# IC_Adapter_2x20_multi.net
KiCad netlist of a schematic drawn in EAGLE
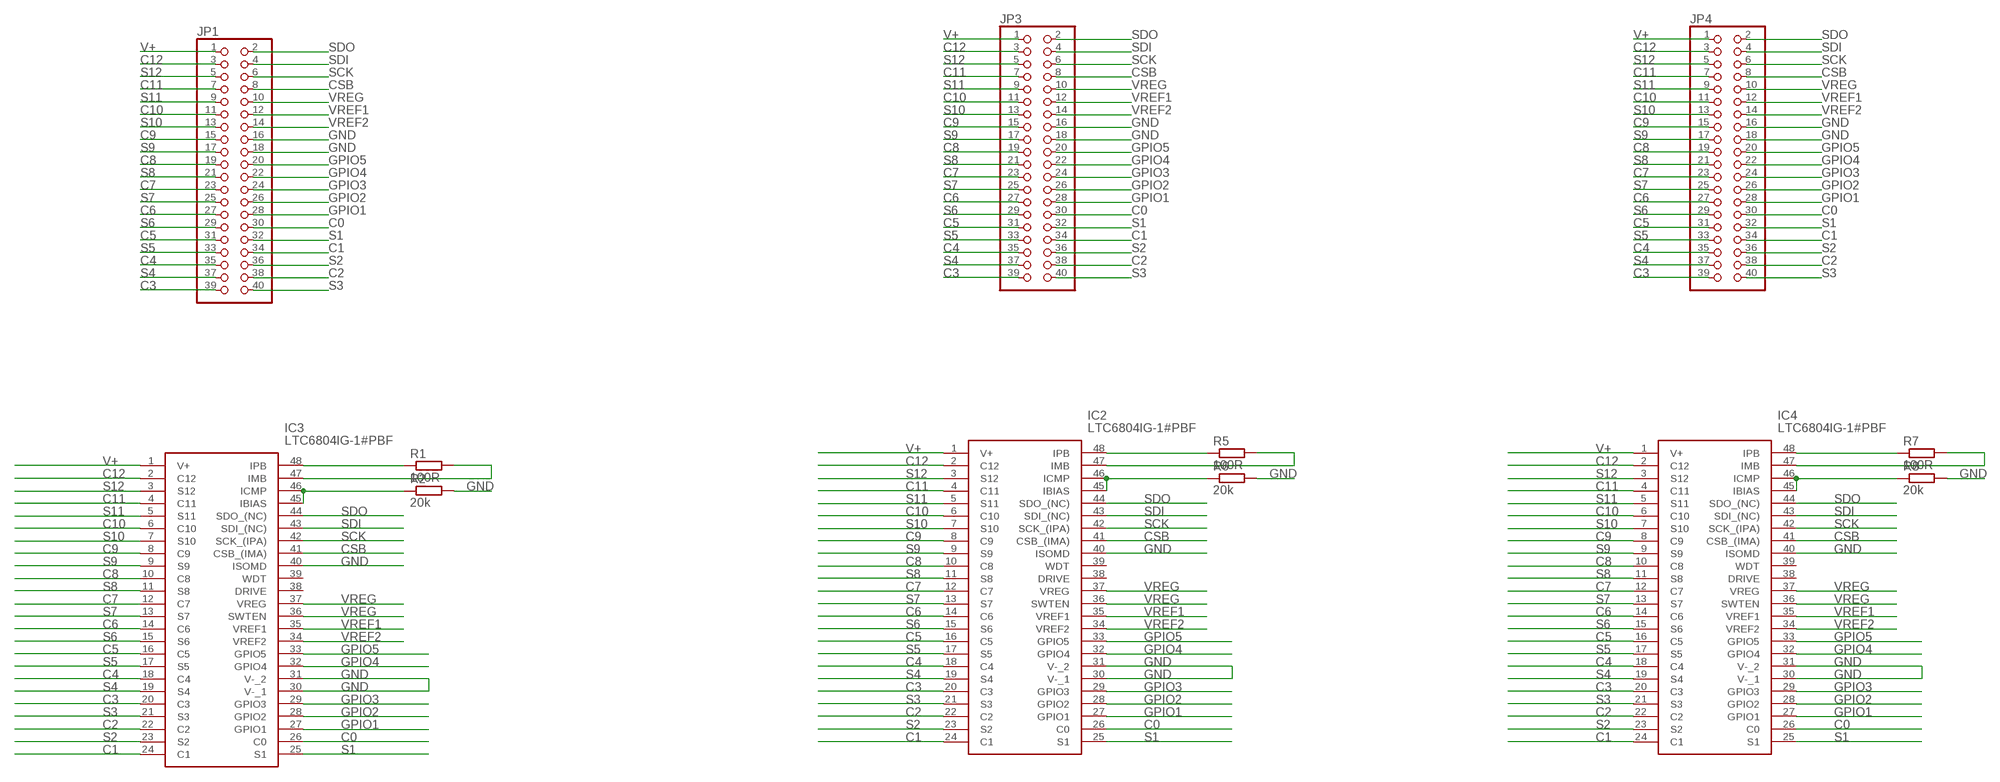
[diagram p0: schematic, sheet 1]

(export (version "E")
  (design (tool "Eeschema 10.0.6"))
  (components
    (comp (ref "IC2")
      (value "LTC6804IG-1#PBF")
      (footprint "eagle-import:SOP50P780X200-48N")
      (fields (field (name "MOUSER_PART_NUMBER") "584-LTC6804IG-1#PBF"))
      (libsource (lib "eagle-import") (part "LTC6804IG-1#PBF"))
    )
    (comp (ref "IC3")
      (value "LTC6804IG-1#PBF")
      (footprint "eagle-import:SOP50P780X200-48N")
      (fields (field (name "MOUSER_PART_NUMBER") "584-LTC6804IG-1#PBF"))
      (libsource (lib "eagle-import") (part "LTC6804IG-1#PBF"))
    )
    (comp (ref "IC4")
      (value "LTC6804IG-1#PBF")
      (footprint "eagle-import:SOP50P780X200-48N")
      (fields (field (name "MOUSER_PART_NUMBER") "584-LTC6804IG-1#PBF"))
      (libsource (lib "eagle-import") (part "LTC6804IG-1#PBF"))
    )
    (comp (ref "JP1")
      (value "PINHD-2X20")
      (footprint "eagle-import:2X20")
      (libsource (lib "eagle-import") (part "PINHD-2X20"))
    )
    (comp (ref "JP3")
      (value "PINHD-2X20")
      (footprint "eagle-import:2X20")
      (libsource (lib "eagle-import") (part "PINHD-2X20"))
    )
    (comp (ref "JP4")
      (value "PINHD-2X20")
      (footprint "eagle-import:2X20")
      (libsource (lib "eagle-import") (part "PINHD-2X20"))
    )
    (comp (ref "R1")
      (value "100R")
      (footprint "eagle-import:R0805")
      (libsource (lib "eagle-import") (part "R-EU_R0805"))
    )
    (comp (ref "R2")
      (value "20k")
      (footprint "eagle-import:R0805")
      (libsource (lib "eagle-import") (part "R-EU_R0805"))
    )
    (comp (ref "R5")
      (value "100R")
      (footprint "eagle-import:R0805")
      (libsource (lib "eagle-import") (part "R-EU_R0805"))
    )
    (comp (ref "R6")
      (value "20k")
      (footprint "eagle-import:R0805")
      (libsource (lib "eagle-import") (part "R-EU_R0805"))
    )
    (comp (ref "R7")
      (value "100R")
      (footprint "eagle-import:R0805")
      (libsource (lib "eagle-import") (part "R-EU_R0805"))
    )
    (comp (ref "R8")
      (value "20k")
      (footprint "eagle-import:R0805")
      (libsource (lib "eagle-import") (part "R-EU_R0805"))
    )
  )
  (nets
    (net (code "1") (name "/C0") (class "Default")
      (node (ref "IC2") (pin "26") (pinfunction "C0_26") (pintype "bidirectional"))
      (node (ref "IC3") (pin "26") (pinfunction "C0_26") (pintype "bidirectional"))
      (node (ref "IC4") (pin "26") (pinfunction "C0_26") (pintype "bidirectional"))
      (node (ref "JP1") (pin "30") (pinfunction "30_30") (pintype "passive"))
      (node (ref "JP3") (pin "30") (pinfunction "30_30") (pintype "passive"))
      (node (ref "JP4") (pin "30") (pinfunction "30_30") (pintype "passive"))
    )
    (net (code "2") (name "/C1") (class "Default")
      (node (ref "IC2") (pin "24") (pinfunction "C1_24") (pintype "bidirectional"))
      (node (ref "IC3") (pin "24") (pinfunction "C1_24") (pintype "bidirectional"))
      (node (ref "IC4") (pin "24") (pinfunction "C1_24") (pintype "bidirectional"))
      (node (ref "JP1") (pin "34") (pinfunction "34_34") (pintype "passive"))
      (node (ref "JP3") (pin "34") (pinfunction "34_34") (pintype "passive"))
      (node (ref "JP4") (pin "34") (pinfunction "34_34") (pintype "passive"))
    )
    (net (code "3") (name "/C2") (class "Default")
      (node (ref "IC2") (pin "22") (pinfunction "C2_22") (pintype "bidirectional"))
      (node (ref "IC3") (pin "22") (pinfunction "C2_22") (pintype "bidirectional"))
      (node (ref "IC4") (pin "22") (pinfunction "C2_22") (pintype "bidirectional"))
      (node (ref "JP1") (pin "38") (pinfunction "38_38") (pintype "passive"))
      (node (ref "JP3") (pin "38") (pinfunction "38_38") (pintype "passive"))
      (node (ref "JP4") (pin "38") (pinfunction "38_38") (pintype "passive"))
    )
    (net (code "4") (name "/C3") (class "Default")
      (node (ref "IC2") (pin "20") (pinfunction "C3_20") (pintype "bidirectional"))
      (node (ref "IC3") (pin "20") (pinfunction "C3_20") (pintype "bidirectional"))
      (node (ref "IC4") (pin "20") (pinfunction "C3_20") (pintype "bidirectional"))
      (node (ref "JP1") (pin "39") (pinfunction "39_39") (pintype "passive"))
      (node (ref "JP3") (pin "39") (pinfunction "39_39") (pintype "passive"))
      (node (ref "JP4") (pin "39") (pinfunction "39_39") (pintype "passive"))
    )
    (net (code "5") (name "/C4") (class "Default")
      (node (ref "IC2") (pin "18") (pinfunction "C4_18") (pintype "bidirectional"))
      (node (ref "IC3") (pin "18") (pinfunction "C4_18") (pintype "bidirectional"))
      (node (ref "IC4") (pin "18") (pinfunction "C4_18") (pintype "bidirectional"))
      (node (ref "JP1") (pin "35") (pinfunction "35_35") (pintype "passive"))
      (node (ref "JP3") (pin "35") (pinfunction "35_35") (pintype "passive"))
      (node (ref "JP4") (pin "35") (pinfunction "35_35") (pintype "passive"))
    )
    (net (code "6") (name "/C5") (class "Default")
      (node (ref "IC2") (pin "16") (pinfunction "C5_16") (pintype "bidirectional"))
      (node (ref "IC3") (pin "16") (pinfunction "C5_16") (pintype "bidirectional"))
      (node (ref "IC4") (pin "16") (pinfunction "C5_16") (pintype "bidirectional"))
      (node (ref "JP1") (pin "31") (pinfunction "31_31") (pintype "passive"))
      (node (ref "JP3") (pin "31") (pinfunction "31_31") (pintype "passive"))
      (node (ref "JP4") (pin "31") (pinfunction "31_31") (pintype "passive"))
    )
    (net (code "7") (name "/C6") (class "Default")
      (node (ref "IC2") (pin "14") (pinfunction "C6_14") (pintype "bidirectional"))
      (node (ref "IC3") (pin "14") (pinfunction "C6_14") (pintype "bidirectional"))
      (node (ref "IC4") (pin "14") (pinfunction "C6_14") (pintype "bidirectional"))
      (node (ref "JP1") (pin "27") (pinfunction "27_27") (pintype "passive"))
      (node (ref "JP3") (pin "27") (pinfunction "27_27") (pintype "passive"))
      (node (ref "JP4") (pin "27") (pinfunction "27_27") (pintype "passive"))
    )
    (net (code "8") (name "/C7") (class "Default")
      (node (ref "IC2") (pin "12") (pinfunction "C7_12") (pintype "bidirectional"))
      (node (ref "IC3") (pin "12") (pinfunction "C7_12") (pintype "bidirectional"))
      (node (ref "IC4") (pin "12") (pinfunction "C7_12") (pintype "bidirectional"))
      (node (ref "JP1") (pin "23") (pinfunction "23_23") (pintype "passive"))
      (node (ref "JP3") (pin "23") (pinfunction "23_23") (pintype "passive"))
      (node (ref "JP4") (pin "23") (pinfunction "23_23") (pintype "passive"))
    )
    (net (code "9") (name "/C8") (class "Default")
      (node (ref "IC2") (pin "10") (pinfunction "C8_10") (pintype "bidirectional"))
      (node (ref "IC3") (pin "10") (pinfunction "C8_10") (pintype "bidirectional"))
      (node (ref "IC4") (pin "10") (pinfunction "C8_10") (pintype "bidirectional"))
      (node (ref "JP1") (pin "19") (pinfunction "19_19") (pintype "passive"))
      (node (ref "JP3") (pin "19") (pinfunction "19_19") (pintype "passive"))
      (node (ref "JP4") (pin "19") (pinfunction "19_19") (pintype "passive"))
    )
    (net (code "10") (name "/C9") (class "Default")
      (node (ref "IC2") (pin "8") (pinfunction "C9_8") (pintype "bidirectional"))
      (node (ref "IC3") (pin "8") (pinfunction "C9_8") (pintype "bidirectional"))
      (node (ref "IC4") (pin "8") (pinfunction "C9_8") (pintype "bidirectional"))
      (node (ref "JP1") (pin "15") (pinfunction "15_15") (pintype "passive"))
      (node (ref "JP3") (pin "15") (pinfunction "15_15") (pintype "passive"))
      (node (ref "JP4") (pin "15") (pinfunction "15_15") (pintype "passive"))
    )
    (net (code "11") (name "/C10") (class "Default")
      (node (ref "IC2") (pin "6") (pinfunction "C10_6") (pintype "bidirectional"))
      (node (ref "IC3") (pin "6") (pinfunction "C10_6") (pintype "bidirectional"))
      (node (ref "IC4") (pin "6") (pinfunction "C10_6") (pintype "bidirectional"))
      (node (ref "JP1") (pin "11") (pinfunction "11_11") (pintype "passive"))
      (node (ref "JP3") (pin "11") (pinfunction "11_11") (pintype "passive"))
      (node (ref "JP4") (pin "11") (pinfunction "11_11") (pintype "passive"))
    )
    (net (code "12") (name "/C11") (class "Default")
      (node (ref "IC2") (pin "4") (pinfunction "C11_4") (pintype "bidirectional"))
      (node (ref "IC3") (pin "4") (pinfunction "C11_4") (pintype "bidirectional"))
      (node (ref "IC4") (pin "4") (pinfunction "C11_4") (pintype "bidirectional"))
      (node (ref "JP1") (pin "7") (pinfunction "7_7") (pintype "passive"))
      (node (ref "JP3") (pin "7") (pinfunction "7_7") (pintype "passive"))
      (node (ref "JP4") (pin "7") (pinfunction "7_7") (pintype "passive"))
    )
    (net (code "13") (name "/C12") (class "Default")
      (node (ref "IC2") (pin "2") (pinfunction "C12_2") (pintype "bidirectional"))
      (node (ref "IC3") (pin "2") (pinfunction "C12_2") (pintype "bidirectional"))
      (node (ref "IC4") (pin "2") (pinfunction "C12_2") (pintype "bidirectional"))
      (node (ref "JP1") (pin "3") (pinfunction "3_3") (pintype "passive"))
      (node (ref "JP3") (pin "3") (pinfunction "3_3") (pintype "passive"))
      (node (ref "JP4") (pin "3") (pinfunction "3_3") (pintype "passive"))
    )
    (net (code "14") (name "/CSB") (class "Default")
      (node (ref "IC2") (pin "41") (pinfunction "CSB_(IMA)_41") (pintype "bidirectional"))
      (node (ref "IC3") (pin "41") (pinfunction "CSB_(IMA)_41") (pintype "bidirectional"))
      (node (ref "IC4") (pin "41") (pinfunction "CSB_(IMA)_41") (pintype "bidirectional"))
      (node (ref "JP1") (pin "8") (pinfunction "8_8") (pintype "passive"))
      (node (ref "JP3") (pin "8") (pinfunction "8_8") (pintype "passive"))
      (node (ref "JP4") (pin "8") (pinfunction "8_8") (pintype "passive"))
    )
    (net (code "15") (name "/GND") (class "Default")
      (node (ref "IC2") (pin "30") (pinfunction "V-_1_30") (pintype "bidirectional"))
      (node (ref "IC2") (pin "31") (pinfunction "V-_2_31") (pintype "bidirectional"))
      (node (ref "IC2") (pin "40") (pinfunction "ISOMD_40") (pintype "bidirectional"))
      (node (ref "IC3") (pin "30") (pinfunction "V-_1_30") (pintype "bidirectional"))
      (node (ref "IC3") (pin "31") (pinfunction "V-_2_31") (pintype "bidirectional"))
      (node (ref "IC3") (pin "40") (pinfunction "ISOMD_40") (pintype "bidirectional"))
      (node (ref "IC4") (pin "30") (pinfunction "V-_1_30") (pintype "bidirectional"))
      (node (ref "IC4") (pin "31") (pinfunction "V-_2_31") (pintype "bidirectional"))
      (node (ref "IC4") (pin "40") (pinfunction "ISOMD_40") (pintype "bidirectional"))
      (node (ref "JP1") (pin "16") (pinfunction "16_16") (pintype "passive"))
      (node (ref "JP1") (pin "18") (pinfunction "18_18") (pintype "passive"))
      (node (ref "JP3") (pin "16") (pinfunction "16_16") (pintype "passive"))
      (node (ref "JP3") (pin "18") (pinfunction "18_18") (pintype "passive"))
      (node (ref "JP4") (pin "16") (pinfunction "16_16") (pintype "passive"))
      (node (ref "JP4") (pin "18") (pinfunction "18_18") (pintype "passive"))
      (node (ref "R2") (pin "2") (pinfunction "2_2") (pintype "passive"))
      (node (ref "R6") (pin "2") (pinfunction "2_2") (pintype "passive"))
      (node (ref "R8") (pin "2") (pinfunction "2_2") (pintype "passive"))
    )
    (net (code "16") (name "/GPIO1") (class "Default")
      (node (ref "IC2") (pin "27") (pinfunction "GPIO1_27") (pintype "bidirectional"))
      (node (ref "IC3") (pin "27") (pinfunction "GPIO1_27") (pintype "bidirectional"))
      (node (ref "IC4") (pin "27") (pinfunction "GPIO1_27") (pintype "bidirectional"))
      (node (ref "JP1") (pin "28") (pinfunction "28_28") (pintype "passive"))
      (node (ref "JP3") (pin "28") (pinfunction "28_28") (pintype "passive"))
      (node (ref "JP4") (pin "28") (pinfunction "28_28") (pintype "passive"))
    )
    (net (code "17") (name "/GPIO2") (class "Default")
      (node (ref "IC2") (pin "28") (pinfunction "GPIO2_28") (pintype "bidirectional"))
      (node (ref "IC3") (pin "28") (pinfunction "GPIO2_28") (pintype "bidirectional"))
      (node (ref "IC4") (pin "28") (pinfunction "GPIO2_28") (pintype "bidirectional"))
      (node (ref "JP1") (pin "26") (pinfunction "26_26") (pintype "passive"))
      (node (ref "JP3") (pin "26") (pinfunction "26_26") (pintype "passive"))
      (node (ref "JP4") (pin "26") (pinfunction "26_26") (pintype "passive"))
    )
    (net (code "18") (name "/GPIO3") (class "Default")
      (node (ref "IC2") (pin "29") (pinfunction "GPIO3_29") (pintype "bidirectional"))
      (node (ref "IC3") (pin "29") (pinfunction "GPIO3_29") (pintype "bidirectional"))
      (node (ref "IC4") (pin "29") (pinfunction "GPIO3_29") (pintype "bidirectional"))
      (node (ref "JP1") (pin "24") (pinfunction "24_24") (pintype "passive"))
      (node (ref "JP3") (pin "24") (pinfunction "24_24") (pintype "passive"))
      (node (ref "JP4") (pin "24") (pinfunction "24_24") (pintype "passive"))
    )
    (net (code "19") (name "/GPIO4") (class "Default")
      (node (ref "IC2") (pin "32") (pinfunction "GPIO4_32") (pintype "bidirectional"))
      (node (ref "IC3") (pin "32") (pinfunction "GPIO4_32") (pintype "bidirectional"))
      (node (ref "IC4") (pin "32") (pinfunction "GPIO4_32") (pintype "bidirectional"))
      (node (ref "JP1") (pin "22") (pinfunction "22_22") (pintype "passive"))
      (node (ref "JP3") (pin "22") (pinfunction "22_22") (pintype "passive"))
      (node (ref "JP4") (pin "22") (pinfunction "22_22") (pintype "passive"))
    )
    (net (code "20") (name "/GPIO5") (class "Default")
      (node (ref "IC2") (pin "33") (pinfunction "GPIO5_33") (pintype "bidirectional"))
      (node (ref "IC3") (pin "33") (pinfunction "GPIO5_33") (pintype "bidirectional"))
      (node (ref "IC4") (pin "33") (pinfunction "GPIO5_33") (pintype "bidirectional"))
      (node (ref "JP1") (pin "20") (pinfunction "20_20") (pintype "passive"))
      (node (ref "JP3") (pin "20") (pinfunction "20_20") (pintype "passive"))
      (node (ref "JP4") (pin "20") (pinfunction "20_20") (pintype "passive"))
    )
    (net (code "21") (name "/S1") (class "Default")
      (node (ref "IC2") (pin "25") (pinfunction "S1_25") (pintype "bidirectional"))
      (node (ref "IC3") (pin "25") (pinfunction "S1_25") (pintype "bidirectional"))
      (node (ref "IC4") (pin "25") (pinfunction "S1_25") (pintype "bidirectional"))
      (node (ref "JP1") (pin "32") (pinfunction "32_32") (pintype "passive"))
      (node (ref "JP3") (pin "32") (pinfunction "32_32") (pintype "passive"))
      (node (ref "JP4") (pin "32") (pinfunction "32_32") (pintype "passive"))
    )
    (net (code "22") (name "/S2") (class "Default")
      (node (ref "IC2") (pin "23") (pinfunction "S2_23") (pintype "bidirectional"))
      (node (ref "IC3") (pin "23") (pinfunction "S2_23") (pintype "bidirectional"))
      (node (ref "IC4") (pin "23") (pinfunction "S2_23") (pintype "bidirectional"))
      (node (ref "JP1") (pin "36") (pinfunction "36_36") (pintype "passive"))
      (node (ref "JP3") (pin "36") (pinfunction "36_36") (pintype "passive"))
      (node (ref "JP4") (pin "36") (pinfunction "36_36") (pintype "passive"))
    )
    (net (code "23") (name "/S3") (class "Default")
      (node (ref "IC2") (pin "21") (pinfunction "S3_21") (pintype "bidirectional"))
      (node (ref "IC3") (pin "21") (pinfunction "S3_21") (pintype "bidirectional"))
      (node (ref "IC4") (pin "21") (pinfunction "S3_21") (pintype "bidirectional"))
      (node (ref "JP1") (pin "40") (pinfunction "40_40") (pintype "passive"))
      (node (ref "JP3") (pin "40") (pinfunction "40_40") (pintype "passive"))
      (node (ref "JP4") (pin "40") (pinfunction "40_40") (pintype "passive"))
    )
    (net (code "24") (name "/S4") (class "Default")
      (node (ref "IC2") (pin "19") (pinfunction "S4_19") (pintype "bidirectional"))
      (node (ref "IC3") (pin "19") (pinfunction "S4_19") (pintype "bidirectional"))
      (node (ref "IC4") (pin "19") (pinfunction "S4_19") (pintype "bidirectional"))
      (node (ref "JP1") (pin "37") (pinfunction "37_37") (pintype "passive"))
      (node (ref "JP3") (pin "37") (pinfunction "37_37") (pintype "passive"))
      (node (ref "JP4") (pin "37") (pinfunction "37_37") (pintype "passive"))
    )
    (net (code "25") (name "/S5") (class "Default")
      (node (ref "IC2") (pin "17") (pinfunction "S5_17") (pintype "bidirectional"))
      (node (ref "IC3") (pin "17") (pinfunction "S5_17") (pintype "bidirectional"))
      (node (ref "IC4") (pin "17") (pinfunction "S5_17") (pintype "bidirectional"))
      (node (ref "JP1") (pin "33") (pinfunction "33_33") (pintype "passive"))
      (node (ref "JP3") (pin "33") (pinfunction "33_33") (pintype "passive"))
      (node (ref "JP4") (pin "33") (pinfunction "33_33") (pintype "passive"))
    )
    (net (code "26") (name "/S6") (class "Default")
      (node (ref "IC2") (pin "15") (pinfunction "S6_15") (pintype "bidirectional"))
      (node (ref "IC3") (pin "15") (pinfunction "S6_15") (pintype "bidirectional"))
      (node (ref "IC4") (pin "15") (pinfunction "S6_15") (pintype "bidirectional"))
      (node (ref "JP1") (pin "29") (pinfunction "29_29") (pintype "passive"))
      (node (ref "JP3") (pin "29") (pinfunction "29_29") (pintype "passive"))
      (node (ref "JP4") (pin "29") (pinfunction "29_29") (pintype "passive"))
    )
    (net (code "27") (name "/S7") (class "Default")
      (node (ref "IC2") (pin "13") (pinfunction "S7_13") (pintype "bidirectional"))
      (node (ref "IC3") (pin "13") (pinfunction "S7_13") (pintype "bidirectional"))
      (node (ref "IC4") (pin "13") (pinfunction "S7_13") (pintype "bidirectional"))
      (node (ref "JP1") (pin "25") (pinfunction "25_25") (pintype "passive"))
      (node (ref "JP3") (pin "25") (pinfunction "25_25") (pintype "passive"))
      (node (ref "JP4") (pin "25") (pinfunction "25_25") (pintype "passive"))
    )
    (net (code "28") (name "/S8") (class "Default")
      (node (ref "IC2") (pin "11") (pinfunction "S8_11") (pintype "bidirectional"))
      (node (ref "IC3") (pin "11") (pinfunction "S8_11") (pintype "bidirectional"))
      (node (ref "IC4") (pin "11") (pinfunction "S8_11") (pintype "bidirectional"))
      (node (ref "JP1") (pin "21") (pinfunction "21_21") (pintype "passive"))
      (node (ref "JP3") (pin "21") (pinfunction "21_21") (pintype "passive"))
      (node (ref "JP4") (pin "21") (pinfunction "21_21") (pintype "passive"))
    )
    (net (code "29") (name "/S9") (class "Default")
      (node (ref "IC2") (pin "9") (pinfunction "S9_9") (pintype "bidirectional"))
      (node (ref "IC3") (pin "9") (pinfunction "S9_9") (pintype "bidirectional"))
      (node (ref "IC4") (pin "9") (pinfunction "S9_9") (pintype "bidirectional"))
      (node (ref "JP1") (pin "17") (pinfunction "17_17") (pintype "passive"))
      (node (ref "JP3") (pin "17") (pinfunction "17_17") (pintype "passive"))
      (node (ref "JP4") (pin "17") (pinfunction "17_17") (pintype "passive"))
    )
    (net (code "30") (name "/S10") (class "Default")
      (node (ref "IC2") (pin "7") (pinfunction "S10_7") (pintype "bidirectional"))
      (node (ref "IC3") (pin "7") (pinfunction "S10_7") (pintype "bidirectional"))
      (node (ref "IC4") (pin "7") (pinfunction "S10_7") (pintype "bidirectional"))
      (node (ref "JP1") (pin "13") (pinfunction "13_13") (pintype "passive"))
      (node (ref "JP3") (pin "13") (pinfunction "13_13") (pintype "passive"))
      (node (ref "JP4") (pin "13") (pinfunction "13_13") (pintype "passive"))
    )
    (net (code "31") (name "/S11") (class "Default")
      (node (ref "IC2") (pin "5") (pinfunction "S11_5") (pintype "bidirectional"))
      (node (ref "IC3") (pin "5") (pinfunction "S11_5") (pintype "bidirectional"))
      (node (ref "IC4") (pin "5") (pinfunction "S11_5") (pintype "bidirectional"))
      (node (ref "JP1") (pin "9") (pinfunction "9_9") (pintype "passive"))
      (node (ref "JP3") (pin "9") (pinfunction "9_9") (pintype "passive"))
      (node (ref "JP4") (pin "9") (pinfunction "9_9") (pintype "passive"))
    )
    (net (code "32") (name "/S12") (class "Default")
      (node (ref "IC2") (pin "3") (pinfunction "S12_3") (pintype "bidirectional"))
      (node (ref "IC3") (pin "3") (pinfunction "S12_3") (pintype "bidirectional"))
      (node (ref "IC4") (pin "3") (pinfunction "S12_3") (pintype "bidirectional"))
      (node (ref "JP1") (pin "5") (pinfunction "5_5") (pintype "passive"))
      (node (ref "JP3") (pin "5") (pinfunction "5_5") (pintype "passive"))
      (node (ref "JP4") (pin "5") (pinfunction "5_5") (pintype "passive"))
    )
    (net (code "33") (name "/SCK") (class "Default")
      (node (ref "IC2") (pin "42") (pinfunction "SCK_(IPA)_42") (pintype "bidirectional"))
      (node (ref "IC3") (pin "42") (pinfunction "SCK_(IPA)_42") (pintype "bidirectional"))
      (node (ref "IC4") (pin "42") (pinfunction "SCK_(IPA)_42") (pintype "bidirectional"))
      (node (ref "JP1") (pin "6") (pinfunction "6_6") (pintype "passive"))
      (node (ref "JP3") (pin "6") (pinfunction "6_6") (pintype "passive"))
      (node (ref "JP4") (pin "6") (pinfunction "6_6") (pintype "passive"))
    )
    (net (code "34") (name "/SDI") (class "Default")
      (node (ref "IC2") (pin "43") (pinfunction "SDI_(NC)_43") (pintype "bidirectional"))
      (node (ref "IC3") (pin "43") (pinfunction "SDI_(NC)_43") (pintype "bidirectional"))
      (node (ref "IC4") (pin "43") (pinfunction "SDI_(NC)_43") (pintype "bidirectional"))
      (node (ref "JP1") (pin "4") (pinfunction "4_4") (pintype "passive"))
      (node (ref "JP3") (pin "4") (pinfunction "4_4") (pintype "passive"))
      (node (ref "JP4") (pin "4") (pinfunction "4_4") (pintype "passive"))
    )
    (net (code "35") (name "/SDO") (class "Default")
      (node (ref "IC2") (pin "44") (pinfunction "SDO_(NC)_44") (pintype "bidirectional"))
      (node (ref "IC3") (pin "44") (pinfunction "SDO_(NC)_44") (pintype "bidirectional"))
      (node (ref "IC4") (pin "44") (pinfunction "SDO_(NC)_44") (pintype "bidirectional"))
      (node (ref "JP1") (pin "2") (pinfunction "2_2") (pintype "passive"))
      (node (ref "JP3") (pin "2") (pinfunction "2_2") (pintype "passive"))
      (node (ref "JP4") (pin "2") (pinfunction "2_2") (pintype "passive"))
    )
    (net (code "36") (name "/V+") (class "Default")
      (node (ref "IC2") (pin "1") (pinfunction "V+_1") (pintype "bidirectional"))
      (node (ref "IC3") (pin "1") (pinfunction "V+_1") (pintype "bidirectional"))
      (node (ref "IC4") (pin "1") (pinfunction "V+_1") (pintype "bidirectional"))
      (node (ref "JP1") (pin "1") (pinfunction "1_1") (pintype "passive"))
      (node (ref "JP3") (pin "1") (pinfunction "1_1") (pintype "passive"))
      (node (ref "JP4") (pin "1") (pinfunction "1_1") (pintype "passive"))
    )
    (net (code "37") (name "/VREF1") (class "Default")
      (node (ref "IC2") (pin "35") (pinfunction "VREF1_35") (pintype "bidirectional"))
      (node (ref "IC3") (pin "35") (pinfunction "VREF1_35") (pintype "bidirectional"))
      (node (ref "IC4") (pin "35") (pinfunction "VREF1_35") (pintype "bidirectional"))
      (node (ref "JP1") (pin "12") (pinfunction "12_12") (pintype "passive"))
      (node (ref "JP3") (pin "12") (pinfunction "12_12") (pintype "passive"))
      (node (ref "JP4") (pin "12") (pinfunction "12_12") (pintype "passive"))
    )
    (net (code "38") (name "/VREF2") (class "Default")
      (node (ref "IC2") (pin "34") (pinfunction "VREF2_34") (pintype "bidirectional"))
      (node (ref "IC3") (pin "34") (pinfunction "VREF2_34") (pintype "bidirectional"))
      (node (ref "IC4") (pin "34") (pinfunction "VREF2_34") (pintype "bidirectional"))
      (node (ref "JP1") (pin "14") (pinfunction "14_14") (pintype "passive"))
      (node (ref "JP3") (pin "14") (pinfunction "14_14") (pintype "passive"))
      (node (ref "JP4") (pin "14") (pinfunction "14_14") (pintype "passive"))
    )
    (net (code "39") (name "/VREG") (class "Default")
      (node (ref "IC2") (pin "36") (pinfunction "SWTEN_36") (pintype "bidirectional"))
      (node (ref "IC2") (pin "37") (pinfunction "VREG_37") (pintype "bidirectional"))
      (node (ref "IC3") (pin "36") (pinfunction "SWTEN_36") (pintype "bidirectional"))
      (node (ref "IC3") (pin "37") (pinfunction "VREG_37") (pintype "bidirectional"))
      (node (ref "IC4") (pin "36") (pinfunction "SWTEN_36") (pintype "bidirectional"))
      (node (ref "IC4") (pin "37") (pinfunction "VREG_37") (pintype "bidirectional"))
      (node (ref "JP1") (pin "10") (pinfunction "10_10") (pintype "passive"))
      (node (ref "JP3") (pin "10") (pinfunction "10_10") (pintype "passive"))
      (node (ref "JP4") (pin "10") (pinfunction "10_10") (pintype "passive"))
    )
    (net (code "40") (name "Net-(IC2-IBIAS)") (class "Default")
      (node (ref "IC2") (pin "45") (pinfunction "IBIAS_45") (pintype "bidirectional"))
      (node (ref "IC2") (pin "46") (pinfunction "ICMP_46") (pintype "bidirectional"))
      (node (ref "R6") (pin "1") (pinfunction "1_1") (pintype "passive"))
    )
    (net (code "41") (name "Net-(IC2-IMB)") (class "Default")
      (node (ref "IC2") (pin "47") (pinfunction "IMB_47") (pintype "bidirectional"))
      (node (ref "R5") (pin "2") (pinfunction "2_2") (pintype "passive"))
    )
    (net (code "42") (name "Net-(IC2-IPB)") (class "Default")
      (node (ref "IC2") (pin "48") (pinfunction "IPB_48") (pintype "bidirectional"))
      (node (ref "R5") (pin "1") (pinfunction "1_1") (pintype "passive"))
    )
    (net (code "43") (name "Net-(IC3-IBIAS)") (class "Default")
      (node (ref "IC3") (pin "45") (pinfunction "IBIAS_45") (pintype "bidirectional"))
      (node (ref "IC3") (pin "46") (pinfunction "ICMP_46") (pintype "bidirectional"))
      (node (ref "R2") (pin "1") (pinfunction "1_1") (pintype "passive"))
    )
    (net (code "44") (name "Net-(IC3-IMB)") (class "Default")
      (node (ref "IC3") (pin "47") (pinfunction "IMB_47") (pintype "bidirectional"))
      (node (ref "R1") (pin "2") (pinfunction "2_2") (pintype "passive"))
    )
    (net (code "45") (name "Net-(IC3-IPB)") (class "Default")
      (node (ref "IC3") (pin "48") (pinfunction "IPB_48") (pintype "bidirectional"))
      (node (ref "R1") (pin "1") (pinfunction "1_1") (pintype "passive"))
    )
    (net (code "46") (name "Net-(IC4-IBIAS)") (class "Default")
      (node (ref "IC4") (pin "45") (pinfunction "IBIAS_45") (pintype "bidirectional"))
      (node (ref "IC4") (pin "46") (pinfunction "ICMP_46") (pintype "bidirectional"))
      (node (ref "R8") (pin "1") (pinfunction "1_1") (pintype "passive"))
    )
    (net (code "47") (name "Net-(IC4-IMB)") (class "Default")
      (node (ref "IC4") (pin "47") (pinfunction "IMB_47") (pintype "bidirectional"))
      (node (ref "R7") (pin "2") (pinfunction "2_2") (pintype "passive"))
    )
    (net (code "48") (name "Net-(IC4-IPB)") (class "Default")
      (node (ref "IC4") (pin "48") (pinfunction "IPB_48") (pintype "bidirectional"))
      (node (ref "R7") (pin "1") (pinfunction "1_1") (pintype "passive"))
    )
    (net (code "49") (name "unconnected-(IC2-DRIVE-Pad38)") (class "Default")
      (node (ref "IC2") (pin "38") (pinfunction "DRIVE_38") (pintype "bidirectional"))
    )
    (net (code "50") (name "unconnected-(IC2-WDT-Pad39)") (class "Default")
      (node (ref "IC2") (pin "39") (pinfunction "WDT_39") (pintype "bidirectional"))
    )
    (net (code "51") (name "unconnected-(IC3-DRIVE-Pad38)") (class "Default")
      (node (ref "IC3") (pin "38") (pinfunction "DRIVE_38") (pintype "bidirectional"))
    )
    (net (code "52") (name "unconnected-(IC3-WDT-Pad39)") (class "Default")
      (node (ref "IC3") (pin "39") (pinfunction "WDT_39") (pintype "bidirectional"))
    )
    (net (code "53") (name "unconnected-(IC4-DRIVE-Pad38)") (class "Default")
      (node (ref "IC4") (pin "38") (pinfunction "DRIVE_38") (pintype "bidirectional"))
    )
    (net (code "54") (name "unconnected-(IC4-WDT-Pad39)") (class "Default")
      (node (ref "IC4") (pin "39") (pinfunction "WDT_39") (pintype "bidirectional"))
    )
  )
)
